# SX70_proto-flash.net
KiCad netlist of a schematic drawn in EAGLE
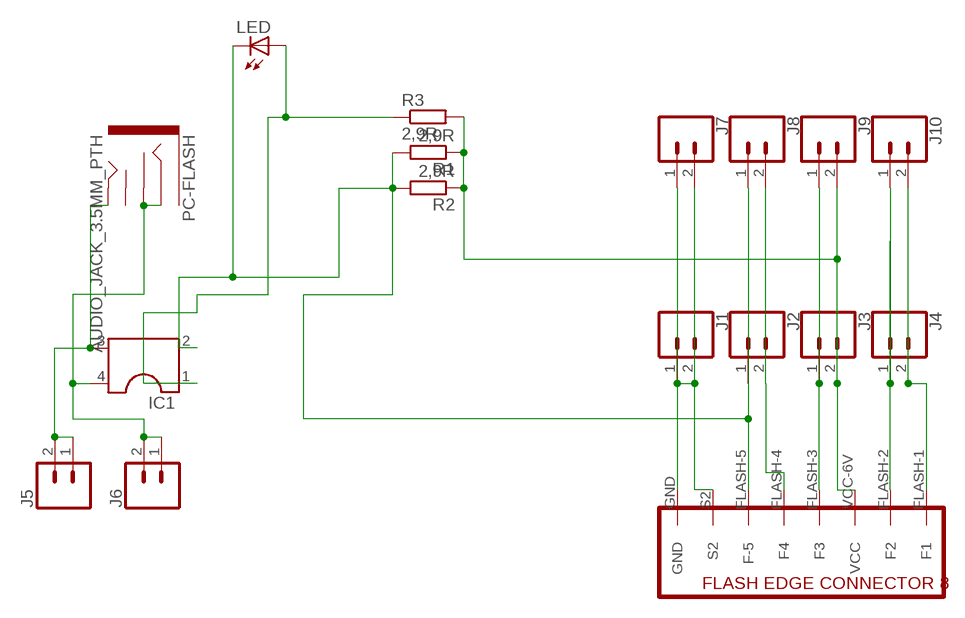
[diagram p0: schematic, sheet 1]

(export (version "E")
  (design (tool "Eeschema 10.0.6"))
  (components
    (comp (ref "FLASH-TESTER")
      (value "SX70-FLASH-EDGE8-MALE")
      (footprint "eagle-import:SX70-FLASH-EDGE8")
      (libsource (lib "eagle-import") (part "SX70-FLASH-EDGE8-MALE"))
    )
    (comp (ref "IC1")
      (value "DIL4")
      (footprint "eagle-import:DIL04")
      (libsource (lib "eagle-import") (part "DIL4"))
    )
    (comp (ref "J1")
      (value "CONN_021X02_NO_SILK")
      (footprint "eagle-import:1X02_NO_SILK")
      (libsource (lib "eagle-import") (part "CONN_021X02_NO_SILK"))
    )
    (comp (ref "J2")
      (value "CONN_021X02_NO_SILK")
      (footprint "eagle-import:1X02_NO_SILK")
      (libsource (lib "eagle-import") (part "CONN_021X02_NO_SILK"))
    )
    (comp (ref "J3")
      (value "CONN_021X02_NO_SILK")
      (footprint "eagle-import:1X02_NO_SILK")
      (libsource (lib "eagle-import") (part "CONN_021X02_NO_SILK"))
    )
    (comp (ref "J4")
      (value "CONN_021X02_NO_SILK")
      (footprint "eagle-import:1X02_NO_SILK")
      (libsource (lib "eagle-import") (part "CONN_021X02_NO_SILK"))
    )
    (comp (ref "J5")
      (value "CONN_021X02_NO_SILK")
      (footprint "eagle-import:1X02_NO_SILK")
      (libsource (lib "eagle-import") (part "CONN_021X02_NO_SILK"))
    )
    (comp (ref "J6")
      (value "CONN_021X02_NO_SILK")
      (footprint "eagle-import:1X02_NO_SILK")
      (libsource (lib "eagle-import") (part "CONN_021X02_NO_SILK"))
    )
    (comp (ref "J7")
      (value "CONN_021X02_NO_SILK")
      (footprint "eagle-import:1X02_NO_SILK")
      (libsource (lib "eagle-import") (part "CONN_021X02_NO_SILK"))
    )
    (comp (ref "J8")
      (value "CONN_021X02_NO_SILK")
      (footprint "eagle-import:1X02_NO_SILK")
      (libsource (lib "eagle-import") (part "CONN_021X02_NO_SILK"))
    )
    (comp (ref "J9")
      (value "CONN_021X02_NO_SILK")
      (footprint "eagle-import:1X02_NO_SILK")
      (libsource (lib "eagle-import") (part "CONN_021X02_NO_SILK"))
    )
    (comp (ref "J10")
      (value "CONN_021X02_NO_SILK")
      (footprint "eagle-import:1X02_NO_SILK")
      (libsource (lib "eagle-import") (part "CONN_021X02_NO_SILK"))
    )
    (comp (ref "LED")
      (value "LED3MM")
      (footprint "eagle-import:LED3MM")
      (libsource (lib "eagle-import") (part "LED3MM"))
    )
    (comp (ref "PC-FLASH")
      (value "AUDIO_JACK_3.5MM_PTH")
      (footprint "eagle-import:AUDIO-JACK")
      (libsource (lib "eagle-import") (part "AUDIO_JACK_3.5MM_PTH"))
    )
    (comp (ref "R1")
      (value "2,9R")
      (footprint "eagle-import:0204_7")
      (libsource (lib "eagle-import") (part "R-EU_0204/7"))
    )
    (comp (ref "R2")
      (value "2,9R")
      (footprint "eagle-import:0204_7")
      (libsource (lib "eagle-import") (part "R-EU_0204/7"))
    )
    (comp (ref "R3")
      (value "2,9R")
      (footprint "eagle-import:0204_7")
      (libsource (lib "eagle-import") (part "R-EU_0204/7"))
    )
  )
  (nets
    (net (code "1") (name "Net-(FLASH-TESTER-F-5)") (class "Default")
      (node (ref "FLASH-TESTER") (pin "FLASH-5") (pinfunction "F-5_FLASH-5") (pintype "bidirectional"))
      (node (ref "IC1") (pin "2") (pinfunction "2_2") (pintype "passive"))
      (node (ref "J2") (pin "1") (pinfunction "1_1") (pintype "passive"))
      (node (ref "J8") (pin "1") (pinfunction "1_1") (pintype "passive"))
      (node (ref "LED") (pin "K") (pinfunction "C_K") (pintype "passive"))
      (node (ref "R1") (pin "2") (pinfunction "2_2") (pintype "passive"))
      (node (ref "R2") (pin "2") (pinfunction "2_2") (pintype "passive"))
    )
    (net (code "2") (name "Net-(FLASH-TESTER-F1)") (class "Default")
      (node (ref "FLASH-TESTER") (pin "FLASH-1") (pinfunction "F1_FLASH-1") (pintype "bidirectional"))
      (node (ref "J10") (pin "2") (pinfunction "2_2") (pintype "passive"))
      (node (ref "J4") (pin "2") (pinfunction "2_2") (pintype "passive"))
    )
    (net (code "3") (name "Net-(FLASH-TESTER-F2)") (class "Default")
      (node (ref "FLASH-TESTER") (pin "FLASH-2") (pinfunction "F2_FLASH-2") (pintype "bidirectional"))
      (node (ref "J10") (pin "1") (pinfunction "1_1") (pintype "passive"))
      (node (ref "J4") (pin "1") (pinfunction "1_1") (pintype "passive"))
    )
    (net (code "4") (name "Net-(FLASH-TESTER-F3)") (class "Default")
      (node (ref "FLASH-TESTER") (pin "FLASH-3") (pinfunction "F3_FLASH-3") (pintype "bidirectional"))
      (node (ref "J3") (pin "1") (pinfunction "1_1") (pintype "passive"))
      (node (ref "J9") (pin "1") (pinfunction "1_1") (pintype "passive"))
    )
    (net (code "5") (name "Net-(FLASH-TESTER-F4)") (class "Default")
      (node (ref "FLASH-TESTER") (pin "FLASH-4") (pinfunction "F4_FLASH-4") (pintype "bidirectional"))
      (node (ref "J2") (pin "2") (pinfunction "2_2") (pintype "passive"))
      (node (ref "J8") (pin "2") (pinfunction "2_2") (pintype "passive"))
    )
    (net (code "6") (name "Net-(FLASH-TESTER-PadGND)") (class "Default")
      (node (ref "FLASH-TESTER") (pin "GND") (pinfunction "GND_GND") (pintype "bidirectional"))
      (node (ref "FLASH-TESTER") (pin "S2") (pinfunction "S2_S2") (pintype "bidirectional"))
      (node (ref "J1") (pin "1") (pinfunction "1_1") (pintype "passive"))
      (node (ref "J1") (pin "2") (pinfunction "2_2") (pintype "passive"))
      (node (ref "J7") (pin "1") (pinfunction "1_1") (pintype "passive"))
      (node (ref "J7") (pin "2") (pinfunction "2_2") (pintype "passive"))
    )
    (net (code "7") (name "Net-(FLASH-TESTER-VCC)") (class "Default")
      (node (ref "FLASH-TESTER") (pin "VCC-6V") (pinfunction "VCC_VCC-6V") (pintype "bidirectional"))
      (node (ref "J3") (pin "2") (pinfunction "2_2") (pintype "passive"))
      (node (ref "J9") (pin "2") (pinfunction "2_2") (pintype "passive"))
      (node (ref "R1") (pin "1") (pinfunction "1_1") (pintype "passive"))
      (node (ref "R2") (pin "1") (pinfunction "1_1") (pintype "passive"))
      (node (ref "R3") (pin "2") (pinfunction "2_2") (pintype "passive"))
    )
    (net (code "8") (name "Net-(IC1-Pad1)") (class "Default")
      (node (ref "IC1") (pin "1") (pinfunction "1_1") (pintype "passive"))
      (node (ref "LED") (pin "A") (pinfunction "A_A") (pintype "passive"))
      (node (ref "R3") (pin "1") (pinfunction "1_1") (pintype "passive"))
    )
    (net (code "9") (name "Net-(IC1-Pad3)") (class "Default")
      (node (ref "IC1") (pin "3") (pinfunction "3_3") (pintype "passive"))
      (node (ref "J5") (pin "1") (pinfunction "1_1") (pintype "passive"))
      (node (ref "J5") (pin "2") (pinfunction "2_2") (pintype "passive"))
      (node (ref "PC-FLASH") (pin "TIP") (pinfunction "TIP_TIP") (pintype "bidirectional"))
    )
    (net (code "10") (name "Net-(IC1-Pad4)") (class "Default")
      (node (ref "IC1") (pin "4") (pinfunction "4_4") (pintype "passive"))
      (node (ref "J6") (pin "1") (pinfunction "1_1") (pintype "passive"))
      (node (ref "J6") (pin "2") (pinfunction "2_2") (pintype "passive"))
      (node (ref "PC-FLASH") (pin "RING") (pinfunction "RING_RING") (pintype "bidirectional"))
      (node (ref "PC-FLASH") (pin "RSH") (pinfunction "RSH_RSH") (pintype "bidirectional"))
    )
    (net (code "11") (name "unconnected-(PC-FLASH-PadSLEEVE)") (class "Default")
      (node (ref "PC-FLASH") (pin "SLEEVE") (pinfunction "SLEEVE_SLEEVE") (pintype "bidirectional"))
    )
    (net (code "12") (name "unconnected-(PC-FLASH-PadTSH)") (class "Default")
      (node (ref "PC-FLASH") (pin "TSH") (pinfunction "TSH_TSH") (pintype "bidirectional"))
    )
  )
)
